# dac_dac4320_4ch.net
KiCad netlist of a schematic drawn in Altium Designer
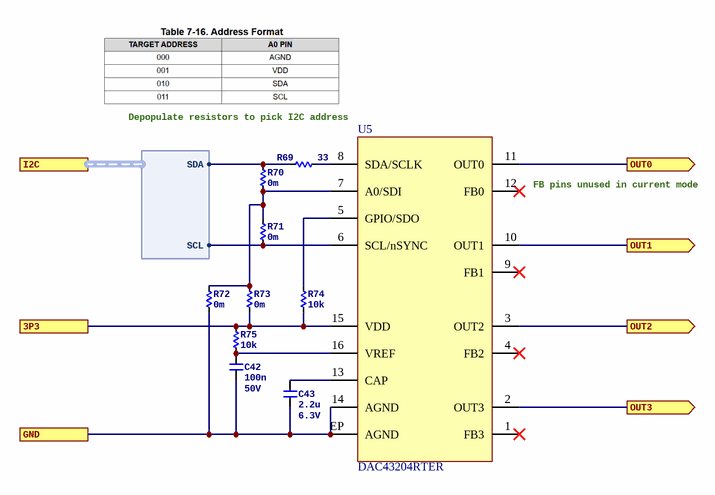
[diagram p0: dac_dac4320_4ch.SchDoc]

(export (version "E")
  (design (tool "Eeschema 10.0.6"))
  (components
    (comp (ref "C42")
      (value "CL05B104KB54PNC")
      (footprint "C0402")
      (fields
        (field (name "CAPACITANCE") "100n")
        (field (name "MANUFACTURER") "Samsung Electro-Mechanics")
        (field (name "VOLTAGE RATING") "50V")
      )
      (libsource (lib "database") (part "__template_cap"))
    )
    (comp (ref "C43")
      (value "GCM188R70J225KE22D")
      (footprint "C0603")
      (fields
        (field (name "CAPACITANCE") "2.2u")
        (field (name "MANUFACTURER") "Murata Electronics")
        (field (name "VOLTAGE RATING") "6.3V")
      )
      (libsource (lib "database") (part "__template_cap"))
    )
    (comp (ref "R69")
      (value "33")
      (footprint "R0402")
      (fields
        (field (name "TOLERANCE") "1%")
        (field (name "MANUFACTURER PART NUMBER") "CRCW040233R0FKED")
        (field (name "MANUFACTURER") "Vishay Intertech")
      )
      (libsource (lib "database") (part "__template_resistor"))
    )
    (comp (ref "R70")
      (value "0m")
      (footprint "R0402")
      (fields
        (field (name "MANUFACTURER PART NUMBER") "0402WGF0000TCE")
        (field (name "MANUFACTURER") "UNI-ROYAL(Uniroyal Elec)")
      )
      (libsource (lib "database") (part "__template_resistor"))
    )
    (comp (ref "R71")
      (value "0m")
      (footprint "R0402")
      (fields
        (field (name "MANUFACTURER PART NUMBER") "0402WGF0000TCE")
        (field (name "MANUFACTURER") "UNI-ROYAL(Uniroyal Elec)")
      )
      (libsource (lib "database") (part "__template_resistor"))
    )
    (comp (ref "R72")
      (value "0m")
      (footprint "R0402")
      (fields
        (field (name "MANUFACTURER PART NUMBER") "0402WGF0000TCE")
        (field (name "MANUFACTURER") "UNI-ROYAL(Uniroyal Elec)")
      )
      (libsource (lib "database") (part "__template_resistor"))
    )
    (comp (ref "R73")
      (value "0m")
      (footprint "R0402")
      (fields
        (field (name "MANUFACTURER PART NUMBER") "0402WGF0000TCE")
        (field (name "MANUFACTURER") "UNI-ROYAL(Uniroyal Elec)")
      )
      (libsource (lib "database") (part "__template_resistor"))
    )
    (comp (ref "R74")
      (value "10k")
      (footprint "R0402")
      (fields
        (field (name "MANUFACTURER PART NUMBER") "0402WGF1002TCE")
        (field (name "MANUFACTURER") "UNI-ROYAL(Uniroyal Elec)")
        (field (name "TOLERANCE") "1%")
      )
      (libsource (lib "database") (part "__template_resistor"))
    )
    (comp (ref "R75")
      (value "10k")
      (footprint "R0402")
      (fields
        (field (name "MANUFACTURER PART NUMBER") "0402WGF1002TCE")
        (field (name "MANUFACTURER") "UNI-ROYAL(Uniroyal Elec)")
        (field (name "TOLERANCE") "1%")
      )
      (libsource (lib "database") (part "__template_resistor"))
    )
    (comp (ref "U5")
      (value "DAC43204RTER")
      (footprint "QFN50P300X300X90-16N")
      (description "IC DAC 8BIT V OR A-OUT 16WQFN")
      (fields (field (name "MANUFACTURER") "Texas Instruments"))
      (libsource (lib "SSCP") (part "DAC_DAC43204RTER"))
    )
  )
  (nets
    (net (code "2") (name "/3P3") (class "Default")
      (node (ref "R73") (pin "1") (pintype "passive"))
      (node (ref "R74") (pin "2") (pintype "passive"))
      (node (ref "R75") (pin "2") (pintype "passive"))
      (node (ref "U5") (pin "15") (pinfunction "VDD_15") (pintype "passive"))
    )
    (net (code "3") (name "/GND") (class "Default")
      (node (ref "C42") (pin "2") (pintype "passive"))
      (node (ref "C43") (pin "2") (pintype "passive"))
      (node (ref "R72") (pin "1") (pintype "passive"))
      (node (ref "U5") (pin "14") (pinfunction "AGND_14") (pintype "passive"))
      (node (ref "U5") (pin "EP") (pinfunction "AGND_EP") (pintype "passive"))
    )
    (net (code "4") (name "/OUT0") (class "Default")
      (node (ref "U5") (pin "11") (pinfunction "OUT0_11") (pintype "passive"))
    )
    (net (code "5") (name "/OUT1") (class "Default")
      (node (ref "U5") (pin "10") (pinfunction "OUT1_10") (pintype "passive"))
    )
    (net (code "6") (name "/OUT2") (class "Default")
      (node (ref "U5") (pin "3") (pinfunction "OUT2_3") (pintype "passive"))
    )
    (net (code "7") (name "/OUT3") (class "Default")
      (node (ref "U5") (pin "2") (pinfunction "OUT3_2") (pintype "passive"))
    )
    (net (code "9") (name "Net-(R69-Pad2)") (class "Default")
      (node (ref "R69") (pin "2") (pintype "passive"))
      (node (ref "R70") (pin "2") (pintype "passive"))
    )
    (net (code "10") (name "Net-(U5-A0{slash}SDI)") (class "Default")
      (node (ref "R70") (pin "1") (pintype "passive"))
      (node (ref "R71") (pin "2") (pintype "passive"))
      (node (ref "R72") (pin "2") (pintype "passive"))
      (node (ref "R73") (pin "2") (pintype "passive"))
      (node (ref "U5") (pin "7") (pinfunction "A0/SDI_7") (pintype "passive"))
    )
    (net (code "11") (name "Net-(U5-CAP)") (class "Default")
      (node (ref "C43") (pin "1") (pintype "passive"))
      (node (ref "U5") (pin "13") (pinfunction "CAP_13") (pintype "passive"))
    )
    (net (code "12") (name "Net-(U5-GPIO{slash}SDO)") (class "Default")
      (node (ref "R74") (pin "1") (pintype "passive"))
      (node (ref "U5") (pin "5") (pinfunction "GPIO/SDO_5") (pintype "passive"))
    )
    (net (code "13") (name "Net-(U5-SCL{slash}nSYNC)") (class "Default")
      (node (ref "R71") (pin "1") (pintype "passive"))
      (node (ref "U5") (pin "6") (pinfunction "SCL/nSYNC_6") (pintype "passive"))
    )
    (net (code "14") (name "Net-(U5-SDA{slash}SCLK)") (class "Default")
      (node (ref "R69") (pin "1") (pintype "passive"))
      (node (ref "U5") (pin "8") (pinfunction "SDA/SCLK_8") (pintype "passive"))
    )
    (net (code "15") (name "Net-(U5-VREF)") (class "Default")
      (node (ref "C42") (pin "1") (pintype "passive"))
      (node (ref "R75") (pin "1") (pintype "passive"))
      (node (ref "U5") (pin "16") (pinfunction "VREF_16") (pintype "passive"))
    )
    (net (code "16") (name "unconnected-(U5-FB0-Pad12)") (class "Default")
      (node (ref "U5") (pin "12") (pinfunction "FB0_12") (pintype "passive+no_connect"))
    )
    (net (code "17") (name "unconnected-(U5-FB1-Pad9)") (class "Default")
      (node (ref "U5") (pin "9") (pinfunction "FB1_9") (pintype "passive+no_connect"))
    )
    (net (code "18") (name "unconnected-(U5-FB2-Pad4)") (class "Default")
      (node (ref "U5") (pin "4") (pinfunction "FB2_4") (pintype "passive+no_connect"))
    )
    (net (code "19") (name "unconnected-(U5-FB3-Pad1)") (class "Default")
      (node (ref "U5") (pin "1") (pinfunction "FB3_1") (pintype "passive+no_connect"))
    )
  )
)
